# ST_LINK_V2-1.net
KiCad netlist of a schematic drawn in Altium Designer
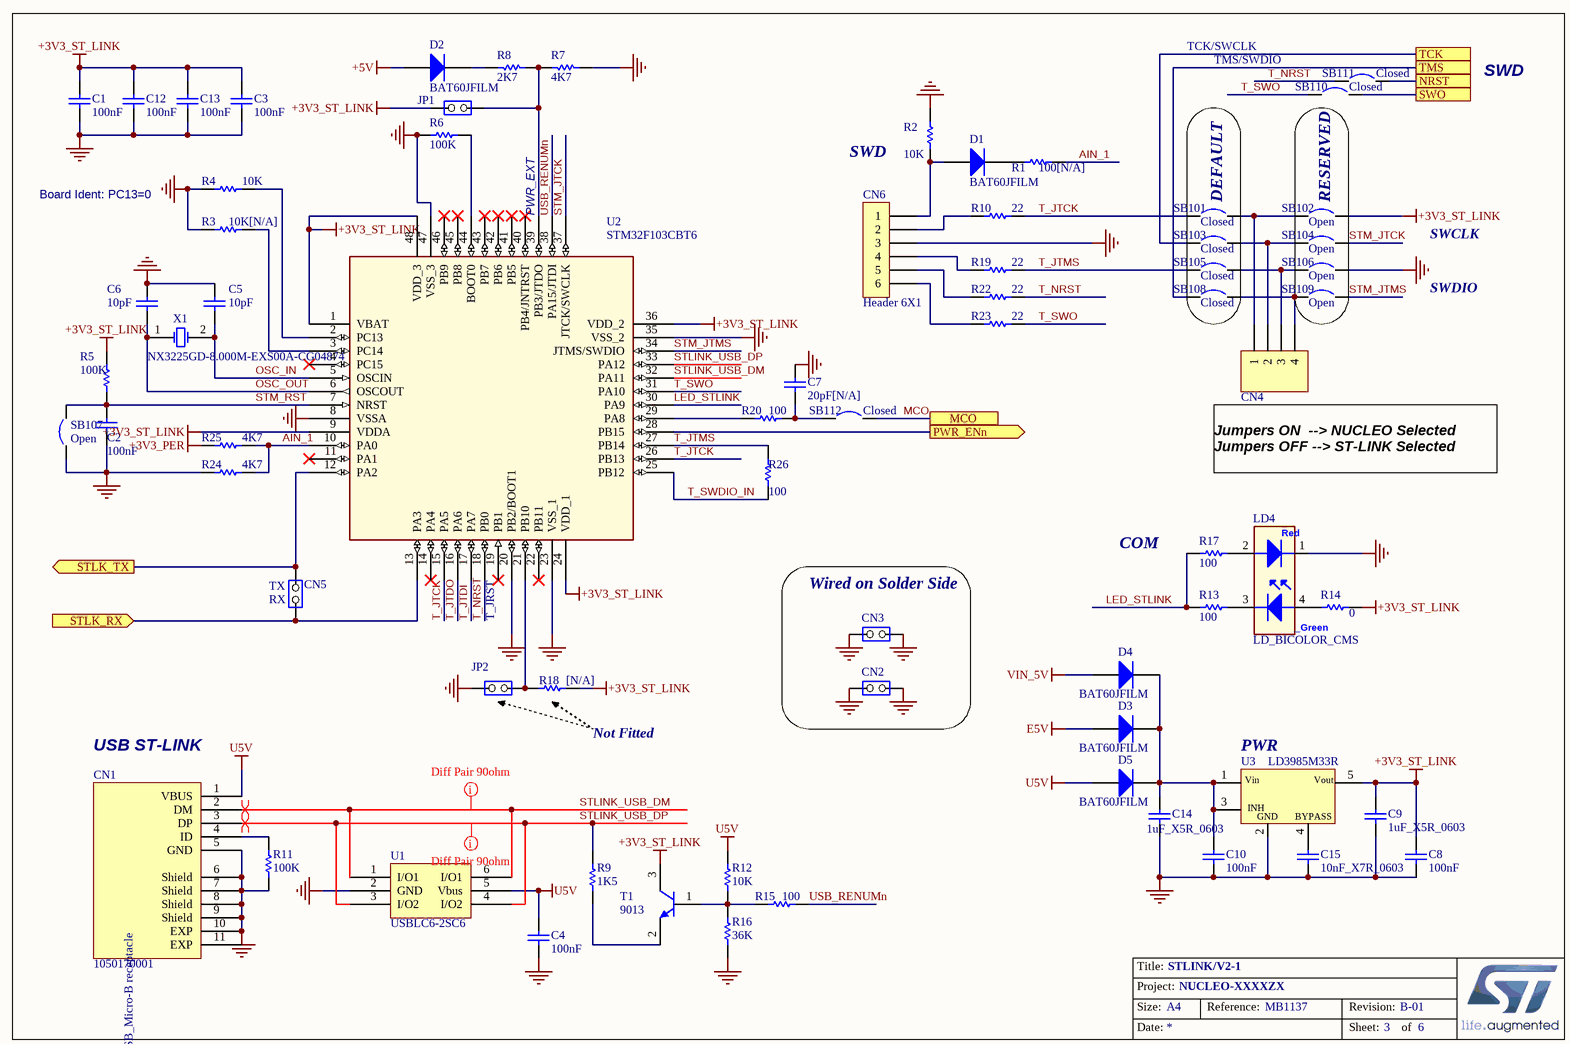
[diagram p0: ST_LINK_V2-1.SCHDOC]

(export (version "E")
  (design (tool "Eeschema 10.0.6"))
  (components
    (comp (ref "C1")
      (value "100nF")
      (footprint "0603C")
      (description "Capacitor 0402 / 0603 / 0805")
      (libsource (lib "MCD_TOOLS") (part "Capacitor_ST"))
    )
    (comp (ref "C2")
      (value "100nF")
      (footprint "0603C")
      (description "Capacitor 0402 / 0603 / 0805")
      (libsource (lib "MCD_TOOLS") (part "Capacitor_ST"))
    )
    (comp (ref "C3")
      (value "100nF")
      (footprint "0603C")
      (description "Capacitor 0402 / 0603 / 0805")
      (libsource (lib "MCD_TOOLS") (part "Capacitor_ST"))
    )
    (comp (ref "C4")
      (value "100nF")
      (footprint "0603C")
      (description "Capacitor 0402 / 0603 / 0805")
      (libsource (lib "MCD_TOOLS") (part "Capacitor_ST"))
    )
    (comp (ref "C5")
      (value "10pF")
      (footprint "0603C")
      (description "Capacitor 0402 / 0603 / 0805")
      (libsource (lib "MCD_TOOLS") (part "Capacitor_ST"))
    )
    (comp (ref "C6")
      (value "10pF")
      (footprint "0603C")
      (description "Capacitor 0402 / 0603 / 0805")
      (libsource (lib "MCD_TOOLS") (part "Capacitor_ST"))
    )
    (comp (ref "C7")
      (value "20pF[N/A]")
      (footprint "0603C")
      (description "Capacitor 0402 / 0603 / 0805")
      (libsource (lib "MCD_TOOLS") (part "Capacitor_ST"))
    )
    (comp (ref "C8")
      (value "100nF")
      (footprint "0603C")
      (description "Capacitor 0402 / 0603 / 0805")
      (libsource (lib "MCD_TOOLS") (part "Capacitor_ST"))
    )
    (comp (ref "C9")
      (value "1uF_X5R_0603")
      (footprint "0603C")
      (description "0603  X5R 1礔")
      (fields (field (name "TOLERANCE") "10%"))
      (libsource (lib "MB963_1") (part "CAP SMD 0603  X5R 1礔 25V 10%"))
    )
    (comp (ref "C10")
      (value "100nF")
      (footprint "0603C")
      (description "Capacitor 0402 / 0603 / 0805")
      (libsource (lib "MCD_TOOLS") (part "Capacitor_ST"))
    )
    (comp (ref "C12")
      (value "100nF")
      (footprint "0603C")
      (description "Capacitor 0402 / 0603 / 0805")
      (libsource (lib "MCD_TOOLS") (part "Capacitor_ST"))
    )
    (comp (ref "C13")
      (value "100nF")
      (footprint "0603C")
      (description "Capacitor 0402 / 0603 / 0805")
      (libsource (lib "MCD_TOOLS") (part "Capacitor_ST"))
    )
    (comp (ref "C14")
      (value "1uF_X5R_0603")
      (footprint "0603C")
      (description "0603  X5R 1礔")
      (fields (field (name "TOLERANCE") "10%"))
      (libsource (lib "MB963_1") (part "CAP SMD 0603  X5R 1礔 25V 10%"))
    )
    (comp (ref "C15")
      (value "10nF_X7R_0603")
      (footprint "0603C")
      (description "0603  X7R 10NF")
      (fields (field (name "TOLERANCE") "10%"))
      (libsource (lib "MB963_1") (part "CAP SMD 0603  X7R 10000PF 50V 10%"))
    )
    (comp (ref "CN1")
      (value "1050170001")
      (footprint "Molex_1050170001")
      (libsource (lib "Smartphone_accessory") (part "1050170001"))
    )
    (comp (ref "CN2") (value "~") (footprint "HDR_1x2_2R54_V_M") (libsource (lib "*") (part "JP2")))
    (comp (ref "CN3") (value "~") (footprint "HDR_1x2_2R54_V_M") (libsource (lib "*") (part "JP2")))
    (comp (ref "CN4")
      (value "Header 4")
      (footprint "HDR_1x4_2R54_V_M")
      (description "Header, 4-Pin, Single row")
      (fields (field (name "PUBLISHER") "Altium Limited"))
      (libsource (lib "Nucleo_64") (part "Header 4"))
    )
    (comp (ref "CN5") (value "~") (footprint "HDR_1x2_2R54_V_M_S") (libsource (lib "MCD_TOOLS") (part "JP2")))
    (comp (ref "CN6")
      (value "Header 6X1")
      (footprint "HDR_1x6_2R54_V_M")
      (description "Header, 6-Pin, Single row")
      (fields (field (name "PUBLISHER") "Altium Limited"))
      (libsource (lib "Nucleo_64") (part "Header 6X1"))
    )
    (comp (ref "D1")
      (value "BAT60JFILM")
      (footprint "SOD-323")
      (libsource (lib "MB1137") (part "BAT60JFILM"))
    )
    (comp (ref "D2")
      (value "BAT60JFILM")
      (footprint "SOD-323")
      (description "Default Diode")
      (fields (field (name "PUBLISHER") "Altium Limited"))
      (libsource (lib "MB1144_1") (part "Diode"))
    )
    (comp (ref "D3")
      (value "BAT60JFILM")
      (footprint "SOD-323")
      (libsource (lib "MB1137") (part "BAT60JFILM"))
    )
    (comp (ref "D4")
      (value "BAT60JFILM")
      (footprint "SOD-323")
      (libsource (lib "MB1137") (part "BAT60JFILM"))
    )
    (comp (ref "D5")
      (value "BAT60JFILM")
      (footprint "SOD-323")
      (libsource (lib "MB1137") (part "BAT60JFILM"))
    )
    (comp (ref "JP1") (value "~") (footprint "HDR_1x2_2R54_V_M_S") (libsource (lib "*") (part "JP2")))
    (comp (ref "JP2") (value "~") (footprint "HDR_1x2_2R54_V_M_S") (libsource (lib "*") (part "JP2")))
    (comp (ref "LD4")
      (value "LD_BICOLOR_CMS")
      (footprint "HSMF-A201")
      (description "Bicolor Led")
      (libsource (lib "MB1137") (part "LD_BICOLOR_CMS"))
    )
    (comp (ref "R1")
      (value "100[N/A]")
      (footprint "0603R")
      (description "Resistor 0402 / 0603 / 0805")
      (libsource (lib "Miscellaneous Devices") (part "Res1"))
    )
    (comp (ref "R2")
      (value "10K")
      (footprint "0603R")
      (description "Resistor 0402 / 0603 / 0805")
      (libsource (lib "Miscellaneous Devices") (part "Res1"))
    )
    (comp (ref "R3")
      (value "10K[N/A]")
      (footprint "0603R")
      (description "Resistor 0402 / 0603 / 0805")
      (libsource (lib "Miscellaneous Devices") (part "Res1"))
    )
    (comp (ref "R4")
      (value "10K")
      (footprint "0603R")
      (description "Resistor 0402 / 0603 / 0805")
      (libsource (lib "Miscellaneous Devices") (part "Res1"))
    )
    (comp (ref "R5")
      (value "100K")
      (footprint "0603R")
      (description "Resistor 0402 / 0603 / 0805")
      (libsource (lib "Miscellaneous Devices") (part "Res1"))
    )
    (comp (ref "R6")
      (value "100K")
      (footprint "0603R")
      (description "Resistor 0402 / 0603 / 0805")
      (libsource (lib "Miscellaneous Devices") (part "Res1"))
    )
    (comp (ref "R7")
      (value "4K7")
      (footprint "0603R")
      (description "Resistor")
      (fields (field (name "PUBLISHER") "Altium Limited"))
      (libsource (lib "") (part "Res1_2"))
    )
    (comp (ref "R8")
      (value "2K7")
      (footprint "0603R")
      (description "Resistor")
      (fields (field (name "PUBLISHER") "Altium Limited"))
      (libsource (lib "") (part "Res1_2"))
    )
    (comp (ref "R9")
      (value "1K5")
      (footprint "0603R")
      (description "Resistor 0402 / 0603 / 0805")
      (libsource (lib "Miscellaneous Devices") (part "Res1"))
    )
    (comp (ref "R10")
      (value "22")
      (footprint "0603R")
      (description "Resistor 0402 / 0603 / 0805")
      (libsource (lib "Miscellaneous Devices") (part "Res1"))
    )
    (comp (ref "R11")
      (value "100K")
      (footprint "0603R")
      (description "Resistor 0402 / 0603 / 0805")
      (libsource (lib "Miscellaneous Devices") (part "Res1"))
    )
    (comp (ref "R12")
      (value "10K")
      (footprint "0603R")
      (description "Resistor")
      (fields (field (name "PUBLISHER") "Altium Limited"))
      (libsource (lib "") (part "Res1_1"))
    )
    (comp (ref "R13")
      (value "100")
      (footprint "0603R")
      (description "Resistor 0402 / 0603 / 0805")
      (libsource (lib "Miscellaneous Devices") (part "Res1"))
    )
    (comp (ref "R14")
      (value "0")
      (footprint "0603R")
      (description "Resistor 0402 / 0603 / 0805")
      (libsource (lib "Miscellaneous Devices") (part "Res1"))
    )
    (comp (ref "R15")
      (value "100")
      (footprint "0603R")
      (description "Resistor 0402 / 0603 / 0805")
      (libsource (lib "Miscellaneous Devices") (part "Res1"))
    )
    (comp (ref "R16")
      (value "36K")
      (footprint "0603R")
      (description "Resistor")
      (fields (field (name "PUBLISHER") "Altium Limited"))
      (libsource (lib "") (part "Res1_1"))
    )
    (comp (ref "R17")
      (value "100")
      (footprint "0603R")
      (description "Resistor 0402 / 0603 / 0805")
      (libsource (lib "Miscellaneous Devices") (part "Res1"))
    )
    (comp (ref "R18")
      (value "[N/A]")
      (footprint "0603R")
      (description "Resistor")
      (fields (field (name "PUBLISHER") "Altium Limited"))
      (libsource (lib "") (part "Res1_1"))
    )
    (comp (ref "R19")
      (value "22")
      (footprint "0603R")
      (description "Resistor 0402 / 0603 / 0805")
      (libsource (lib "Miscellaneous Devices") (part "Res1"))
    )
    (comp (ref "R20")
      (value "100")
      (footprint "0603R")
      (description "Resistor 0402 / 0603 / 0805")
      (libsource (lib "Miscellaneous Devices") (part "Res1"))
    )
    (comp (ref "R22")
      (value "22")
      (footprint "0603R")
      (description "Resistor 0402 / 0603 / 0805")
      (libsource (lib "Miscellaneous Devices") (part "Res1"))
    )
    (comp (ref "R23")
      (value "22")
      (footprint "0603R")
      (description "Resistor 0402 / 0603 / 0805")
      (libsource (lib "Miscellaneous Devices") (part "Res1"))
    )
    (comp (ref "R24")
      (value "4K7")
      (footprint "0603R")
      (description "Resistor 0402 / 0603 / 0805")
      (libsource (lib "Miscellaneous Devices") (part "Res1"))
    )
    (comp (ref "R25")
      (value "4K7")
      (footprint "0603R")
      (description "Resistor 0402 / 0603 / 0805")
      (libsource (lib "Miscellaneous Devices") (part "Res1"))
    )
    (comp (ref "R26")
      (value "100")
      (footprint "0603R")
      (description "Resistor 0402 / 0603 / 0805")
      (libsource (lib "Miscellaneous Devices") (part "Res1"))
    )
    (comp (ref "SB101")
      (value "Closed")
      (footprint "SB_0603")
      (description "Circuit Breaker")
      (fields (field (name "PUBLISHER") "Altium Limited"))
      (libsource (lib "MB1167") (part "Circuit Breaker_close"))
    )
    (comp (ref "SB102")
      (value "Open")
      (footprint "SB_0603")
      (description "Circuit Breaker")
      (fields (field (name "PUBLISHER") "Altium Limited"))
      (libsource (lib "MB1167") (part "Circuit Breaker"))
    )
    (comp (ref "SB103")
      (value "Closed")
      (footprint "SB_0603")
      (description "Circuit Breaker")
      (fields (field (name "PUBLISHER") "Altium Limited"))
      (libsource (lib "MB1167") (part "Circuit Breaker_close"))
    )
    (comp (ref "SB104")
      (value "Open")
      (footprint "SB_0603")
      (description "Circuit Breaker")
      (fields (field (name "PUBLISHER") "Altium Limited"))
      (libsource (lib "MB1167") (part "Circuit Breaker"))
    )
    (comp (ref "SB105")
      (value "Closed")
      (footprint "SB_0603")
      (description "Circuit Breaker")
      (fields (field (name "PUBLISHER") "Altium Limited"))
      (libsource (lib "MB1167") (part "Circuit Breaker_close"))
    )
    (comp (ref "SB106")
      (value "Open")
      (footprint "SB_0603")
      (description "Circuit Breaker")
      (fields (field (name "PUBLISHER") "Altium Limited"))
      (libsource (lib "MB1167") (part "Circuit Breaker"))
    )
    (comp (ref "SB107")
      (value "Open")
      (footprint "SB_0603")
      (description "Circuit Breaker")
      (fields (field (name "PUBLISHER") "Altium Limited"))
      (libsource (lib "MB1167") (part "Circuit Breaker"))
    )
    (comp (ref "SB108")
      (value "Closed")
      (footprint "SB_0603")
      (description "Circuit Breaker")
      (fields (field (name "PUBLISHER") "Altium Limited"))
      (libsource (lib "MB1167") (part "Circuit Breaker_close"))
    )
    (comp (ref "SB109")
      (value "Open")
      (footprint "SB_0603")
      (description "Circuit Breaker")
      (fields (field (name "PUBLISHER") "Altium Limited"))
      (libsource (lib "MB1167") (part "Circuit Breaker"))
    )
    (comp (ref "SB110")
      (value "Closed")
      (footprint "SB_0603")
      (description "Circuit Breaker")
      (fields (field (name "PUBLISHER") "Altium Limited"))
      (libsource (lib "MB1167") (part "Circuit Breaker_close"))
    )
    (comp (ref "SB111")
      (value "Closed")
      (footprint "SB_0603")
      (description "Circuit Breaker")
      (fields (field (name "PUBLISHER") "Altium Limited"))
      (libsource (lib "MB1167") (part "Circuit Breaker_close"))
    )
    (comp (ref "SB112")
      (value "Closed")
      (footprint "SB_0603")
      (description "Circuit Breaker")
      (fields (field (name "PUBLISHER") "Altium Limited"))
      (libsource (lib "MB1167") (part "Circuit Breaker_close"))
    )
    (comp (ref "T1")
      (value "9013")
      (footprint "SOT-23")
      (description "NPN Bipolar Transistor")
      (fields (field (name "PUBLISHER") "Altium Limited"))
      (libsource (lib "MB1167") (part "NPN"))
    )
    (comp (ref "U1")
      (value "USBLC6-2SC6")
      (footprint "SOT23-6L")
      (libsource (lib "MB1137") (part "USBLC6-2SC6"))
    )
    (comp (ref "U2")
      (value "STM32F103CBT6")
      (footprint "LQFP48_0R5_7x7")
      (description "Medium-density performance line ARM-based 32-bit MCU with 64KB Flash")
      (libsource (lib "Nucleo_64") (part "STM32F103CBT6"))
    )
    (comp (ref "U3")
      (value "LD3985M33R")
      (footprint "SOT-23-5L")
      (description "Ultra low drop-low noise BiCMOS voltage, regulators low ESR capacitors compatible")
      (libsource (lib "MCD_TOOLS") (part "LD3985M33R"))
    )
    (comp (ref "X1")
      (value "NX3225GD-8.000M-EXS00A-CG04874")
      (footprint "OSC_2SM_3R2x2R5")
      (description "Crystal Oscillator")
      (fields (field (name "PUBLISHER") "Altium Limited"))
      (libsource (lib "MB963_1") (part "XTAL"))
    )
  )
  (nets
    (net (code "1") (name "+3V3_PER") (class "Default")
      (node (ref "R25") (pin "1") (pinfunction "1_1") (pintype "passive"))
    )
    (net (code "2") (name "+3V3_ST_LINK") (class "Default")
      (node (ref "C1") (pin "2") (pinfunction "2_2") (pintype "passive"))
      (node (ref "C12") (pin "2") (pinfunction "2_2") (pintype "passive"))
      (node (ref "C13") (pin "2") (pinfunction "2_2") (pintype "passive"))
      (node (ref "C3") (pin "2") (pinfunction "2_2") (pintype "passive"))
      (node (ref "C8") (pin "2") (pinfunction "2_2") (pintype "passive"))
      (node (ref "C9") (pin "1") (pinfunction "1_1") (pintype "passive"))
      (node (ref "JP1") (pin "1") (pinfunction "COMMON_1") (pintype "passive"))
      (node (ref "R14") (pin "2") (pinfunction "2_2") (pintype "passive"))
      (node (ref "R18") (pin "1") (pinfunction "1_1") (pintype "passive"))
      (node (ref "R5") (pin "2") (pinfunction "2_2") (pintype "passive"))
      (node (ref "SB102") (pin "2") (pinfunction "2_2") (pintype "passive"))
      (node (ref "T1") (pin "3") (pinfunction "C_3") (pintype "passive"))
      (node (ref "U2") (pin "1") (pinfunction "VBAT_1") (pintype "power_in"))
      (node (ref "U2") (pin "24") (pinfunction "VDD_1_24") (pintype "power_in"))
      (node (ref "U2") (pin "36") (pinfunction "VDD_2_36") (pintype "power_in"))
      (node (ref "U2") (pin "48") (pinfunction "VDD_3_48") (pintype "power_in"))
      (node (ref "U2") (pin "9") (pinfunction "VDDA_9") (pintype "power_in"))
      (node (ref "U3") (pin "5") (pinfunction "Vout_5") (pintype "passive"))
    )
    (net (code "3") (name "+5V") (class "Default")
      (node (ref "D2") (pin "1") (pinfunction "A_1") (pintype "passive"))
    )
    (net (code "4") (name "/AIN_1") (class "Default")
      (node (ref "R1") (pin "2") (pinfunction "2_2") (pintype "passive"))
      (node (ref "R24") (pin "2") (pinfunction "2_2") (pintype "passive"))
      (node (ref "R25") (pin "2") (pinfunction "2_2") (pintype "passive"))
      (node (ref "U2") (pin "10") (pinfunction "PA0_10") (pintype "bidirectional"))
    )
    (net (code "5") (name "/LED_STLINK") (class "Default")
      (node (ref "R13") (pin "1") (pinfunction "1_1") (pintype "passive"))
      (node (ref "R17") (pin "1") (pinfunction "1_1") (pintype "passive"))
      (node (ref "U2") (pin "30") (pinfunction "PA9_30") (pintype "bidirectional"))
    )
    (net (code "6") (name "/MCO") (class "Default")
      (node (ref "SB112") (pin "2") (pinfunction "2_2") (pintype "passive"))
    )
    (net (code "7") (name "/NRST") (class "Default")
      (node (ref "SB111") (pin "2") (pinfunction "2_2") (pintype "passive"))
    )
    (net (code "8") (name "/OSC_IN") (class "Default")
      (node (ref "C5") (pin "1") (pinfunction "1_1") (pintype "passive"))
      (node (ref "U2") (pin "5") (pinfunction "OSCIN_5") (pintype "input"))
      (node (ref "X1") (pin "2") (pinfunction "OSC2_2") (pintype "passive"))
    )
    (net (code "9") (name "/OSC_OUT") (class "Default")
      (node (ref "C6") (pin "1") (pinfunction "1_1") (pintype "passive"))
      (node (ref "U2") (pin "6") (pinfunction "OSCOUT_6") (pintype "output"))
      (node (ref "X1") (pin "1") (pinfunction "OSC1_1") (pintype "passive"))
    )
    (net (code "10") (name "/PWR_ENn") (class "Default")
      (node (ref "U2") (pin "28") (pinfunction "PB15_28") (pintype "bidirectional"))
    )
    (net (code "11") (name "/STLINK_USB_DM") (class "Default")
      (node (ref "CN1") (pin "2") (pinfunction "DM_2") (pintype "passive"))
      (node (ref "U1") (pin "1") (pinfunction "I/O1_1") (pintype "passive"))
      (node (ref "U1") (pin "6") (pinfunction "I/O1_6") (pintype "passive"))
      (node (ref "U2") (pin "32") (pinfunction "PA11_32") (pintype "bidirectional"))
    )
    (net (code "12") (name "/STLINK_USB_DP") (class "Default")
      (node (ref "CN1") (pin "3") (pinfunction "DP_3") (pintype "passive"))
      (node (ref "R9") (pin "1") (pinfunction "1_1") (pintype "passive"))
      (node (ref "U1") (pin "3") (pinfunction "I/O2_3") (pintype "passive"))
      (node (ref "U1") (pin "4") (pinfunction "I/O2_4") (pintype "passive"))
      (node (ref "U2") (pin "33") (pinfunction "PA12_33") (pintype "bidirectional"))
    )
    (net (code "13") (name "/STLK_RX") (class "Default")
      (node (ref "CN5") (pin "1") (pinfunction "COMMON_1") (pintype "passive"))
      (node (ref "U2") (pin "13") (pinfunction "PA3_13") (pintype "bidirectional"))
    )
    (net (code "14") (name "/STLK_TX") (class "Default")
      (node (ref "CN5") (pin "2") (pinfunction "NO_2") (pintype "passive"))
      (node (ref "U2") (pin "12") (pinfunction "PA2_12") (pintype "bidirectional"))
    )
    (net (code "15") (name "/STM_JTCK") (class "Default")
      (node (ref "SB104") (pin "2") (pinfunction "2_2") (pintype "passive"))
      (node (ref "U2") (pin "37") (pinfunction "JTCK/SWCLK_37") (pintype "bidirectional"))
    )
    (net (code "16") (name "/STM_JTMS") (class "Default")
      (node (ref "SB109") (pin "2") (pinfunction "2_2") (pintype "passive"))
      (node (ref "U2") (pin "34") (pinfunction "JTMS/SWDIO_34") (pintype "bidirectional"))
    )
    (net (code "17") (name "/STM_RST") (class "Default")
      (node (ref "C2") (pin "2") (pinfunction "2_2") (pintype "passive"))
      (node (ref "R5") (pin "1") (pinfunction "1_1") (pintype "passive"))
      (node (ref "SB107") (pin "2") (pinfunction "2_2") (pintype "passive"))
      (node (ref "U2") (pin "7") (pinfunction "NRST_7") (pintype "input"))
    )
    (net (code "18") (name "/SWO") (class "Default")
      (node (ref "SB110") (pin "2") (pinfunction "2_2") (pintype "passive"))
    )
    (net (code "19") (name "/TCK") (class "Default")
      (node (ref "SB103") (pin "1") (pinfunction "1_1") (pintype "passive"))
    )
    (net (code "20") (name "/TMS") (class "Default")
      (node (ref "SB108") (pin "1") (pinfunction "1_1") (pintype "passive"))
    )
    (net (code "21") (name "/T_JTCK") (class "Default")
      (node (ref "R10") (pin "2") (pinfunction "2_2") (pintype "passive"))
      (node (ref "SB101") (pin "1") (pinfunction "1_1") (pintype "passive"))
      (node (ref "U2") (pin "15") (pinfunction "PA5_15") (pintype "bidirectional"))
      (node (ref "U2") (pin "26") (pinfunction "PB13_26") (pintype "bidirectional"))
    )
    (net (code "22") (name "/T_JTDI") (class "Default")
      (node (ref "U2") (pin "17") (pinfunction "PA7_17") (pintype "bidirectional"))
    )
    (net (code "23") (name "/T_JTDO") (class "Default")
      (node (ref "U2") (pin "16") (pinfunction "PA6_16") (pintype "bidirectional"))
    )
    (net (code "24") (name "/T_JTMS") (class "Default")
      (node (ref "R19") (pin "2") (pinfunction "2_2") (pintype "passive"))
      (node (ref "R26") (pin "2") (pinfunction "2_2") (pintype "passive"))
      (node (ref "SB105") (pin "1") (pinfunction "1_1") (pintype "passive"))
      (node (ref "U2") (pin "27") (pinfunction "PB14_27") (pintype "bidirectional"))
    )
    (net (code "25") (name "/T_NRST") (class "Default")
      (node (ref "R22") (pin "2") (pinfunction "2_2") (pintype "passive"))
      (node (ref "SB111") (pin "1") (pinfunction "1_1") (pintype "passive"))
      (node (ref "U2") (pin "18") (pinfunction "PB0_18") (pintype "bidirectional"))
    )
    (net (code "26") (name "/T_SWDIO_IN") (class "Default")
      (node (ref "R26") (pin "1") (pinfunction "1_1") (pintype "passive"))
      (node (ref "U2") (pin "25") (pinfunction "PB12_25") (pintype "bidirectional"))
    )
    (net (code "27") (name "/T_SWO") (class "Default")
      (node (ref "R23") (pin "2") (pinfunction "2_2") (pintype "passive"))
      (node (ref "SB110") (pin "1") (pinfunction "1_1") (pintype "passive"))
      (node (ref "U2") (pin "31") (pinfunction "PA10_31") (pintype "bidirectional"))
    )
    (net (code "28") (name "/USB_RENUMn") (class "Default")
      (node (ref "R15") (pin "2") (pinfunction "2_2") (pintype "passive"))
      (node (ref "U2") (pin "38") (pinfunction "PA15/JTDI_38") (pintype "bidirectional"))
    )
    (net (code "29") (name "E5V") (class "Default")
      (node (ref "D3") (pin "1") (pinfunction "A_1") (pintype "passive"))
    )
    (net (code "30") (name "GND") (class "Default")
      (node (ref "C1") (pin "1") (pinfunction "1_1") (pintype "passive"))
      (node (ref "C10") (pin "1") (pinfunction "1_1") (pintype "passive"))
      (node (ref "C12") (pin "1") (pinfunction "1_1") (pintype "passive"))
      (node (ref "C13") (pin "1") (pinfunction "1_1") (pintype "passive"))
      (node (ref "C14") (pin "1") (pinfunction "1_1") (pintype "passive"))
      (node (ref "C15") (pin "1") (pinfunction "1_1") (pintype "passive"))
      (node (ref "C2") (pin "1") (pinfunction "1_1") (pintype "passive"))
      (node (ref "C3") (pin "1") (pinfunction "1_1") (pintype "passive"))
      (node (ref "C4") (pin "1") (pinfunction "1_1") (pintype "passive"))
      (node (ref "C5") (pin "2") (pinfunction "2_2") (pintype "passive"))
      (node (ref "C6") (pin "2") (pinfunction "2_2") (pintype "passive"))
      (node (ref "C7") (pin "2") (pinfunction "2_2") (pintype "passive"))
      (node (ref "C8") (pin "1") (pinfunction "1_1") (pintype "passive"))
      (node (ref "C9") (pin "2") (pinfunction "2_2") (pintype "passive"))
      (node (ref "CN1") (pin "10") (pinfunction "EXP_10") (pintype "passive"))
      (node (ref "CN1") (pin "5") (pinfunction "GND_5") (pintype "passive"))
      (node (ref "CN1") (pin "6") (pinfunction "Shield_6") (pintype "passive"))
      (node (ref "CN1") (pin "7") (pinfunction "Shield_7") (pintype "passive"))
      (node (ref "CN1") (pin "8") (pinfunction "Shield_8") (pintype "passive"))
      (node (ref "CN1") (pin "9") (pinfunction "Shield_9") (pintype "passive"))
      (node (ref "CN2") (pin "1") (pinfunction "COMMON_1") (pintype "passive"))
      (node (ref "CN2") (pin "2") (pinfunction "NO_2") (pintype "passive"))
      (node (ref "CN3") (pin "1") (pinfunction "COMMON_1") (pintype "passive"))
      (node (ref "CN3") (pin "2") (pinfunction "NO_2") (pintype "passive"))
      (node (ref "CN6") (pin "3") (pinfunction "3_3") (pintype "passive"))
      (node (ref "JP2") (pin "1") (pinfunction "COMMON_1") (pintype "passive"))
      (node (ref "LD4") (pin "1") (pinfunction "1_1") (pintype "passive"))
      (node (ref "R11") (pin "2") (pinfunction "2_2") (pintype "passive"))
      (node (ref "R16") (pin "1") (pinfunction "1_1") (pintype "passive"))
      (node (ref "R2") (pin "2") (pinfunction "2_2") (pintype "passive"))
      (node (ref "R24") (pin "1") (pinfunction "1_1") (pintype "passive"))
      (node (ref "R3") (pin "1") (pinfunction "1_1") (pintype "passive"))
      (node (ref "R4") (pin "1") (pinfunction "1_1") (pintype "passive"))
      (node (ref "R6") (pin "1") (pinfunction "1_1") (pintype "passive"))
      (node (ref "R7") (pin "2") (pinfunction "2_2") (pintype "passive"))
      (node (ref "SB106") (pin "2") (pinfunction "2_2") (pintype "passive"))
      (node (ref "SB107") (pin "1") (pinfunction "1_1") (pintype "passive"))
      (node (ref "U1") (pin "2") (pinfunction "GND_2") (pintype "passive"))
      (node (ref "U2") (pin "20") (pinfunction "PB2/BOOT1_20") (pintype "bidirectional"))
      (node (ref "U2") (pin "23") (pinfunction "VSS_1_23") (pintype "power_in"))
      (node (ref "U2") (pin "35") (pinfunction "VSS_2_35") (pintype "power_in"))
      (node (ref "U2") (pin "47") (pinfunction "VSS_3_47") (pintype "power_in"))
      (node (ref "U2") (pin "8") (pinfunction "VSSA_8") (pintype "power_in"))
      (node (ref "U3") (pin "2") (pinfunction "GND_2") (pintype "passive"))
    )
    (net (code "31") (name "Net-(C7-Pad1)") (class "Default")
      (node (ref "C7") (pin "1") (pinfunction "1_1") (pintype "passive"))
      (node (ref "R20") (pin "2") (pinfunction "2_2") (pintype "passive"))
      (node (ref "SB112") (pin "1") (pinfunction "1_1") (pintype "passive"))
    )
    (net (code "32") (name "Net-(CN1-ID)") (class "Default")
      (node (ref "CN1") (pin "4") (pinfunction "ID_4") (pintype "passive"))
      (node (ref "R11") (pin "1") (pinfunction "1_1") (pintype "passive"))
    )
    (net (code "33") (name "Net-(CN4-Pad1)") (class "Default")
      (node (ref "CN4") (pin "1") (pinfunction "1_1") (pintype "passive"))
      (node (ref "SB101") (pin "2") (pinfunction "2_2") (pintype "passive"))
      (node (ref "SB102") (pin "1") (pinfunction "1_1") (pintype "passive"))
    )
    (net (code "34") (name "Net-(CN4-Pad2)") (class "Default")
      (node (ref "CN4") (pin "2") (pinfunction "2_2") (pintype "passive"))
      (node (ref "SB103") (pin "2") (pinfunction "2_2") (pintype "passive"))
      (node (ref "SB104") (pin "1") (pinfunction "1_1") (pintype "passive"))
    )
    (net (code "35") (name "Net-(CN4-Pad3)") (class "Default")
      (node (ref "CN4") (pin "3") (pinfunction "3_3") (pintype "passive"))
      (node (ref "SB105") (pin "2") (pinfunction "2_2") (pintype "passive"))
      (node (ref "SB106") (pin "1") (pinfunction "1_1") (pintype "passive"))
    )
    (net (code "36") (name "Net-(CN4-Pad4)") (class "Default")
      (node (ref "CN4") (pin "4") (pinfunction "4_4") (pintype "passive"))
      (node (ref "SB108") (pin "2") (pinfunction "2_2") (pintype "passive"))
      (node (ref "SB109") (pin "1") (pinfunction "1_1") (pintype "passive"))
    )
    (net (code "37") (name "Net-(CN6-Pad2)") (class "Default")
      (node (ref "CN6") (pin "2") (pinfunction "2_2") (pintype "passive"))
      (node (ref "R10") (pin "1") (pinfunction "1_1") (pintype "passive"))
    )
    (net (code "38") (name "Net-(CN6-Pad4)") (class "Default")
      (node (ref "CN6") (pin "4") (pinfunction "4_4") (pintype "passive"))
      (node (ref "R19") (pin "1") (pinfunction "1_1") (pintype "passive"))
    )
    (net (code "39") (name "Net-(CN6-Pad5)") (class "Default")
      (node (ref "CN6") (pin "5") (pinfunction "5_5") (pintype "passive"))
      (node (ref "R22") (pin "1") (pinfunction "1_1") (pintype "passive"))
    )
    (net (code "40") (name "Net-(CN6-Pad6)") (class "Default")
      (node (ref "CN6") (pin "6") (pinfunction "6_6") (pintype "passive"))
      (node (ref "R23") (pin "1") (pinfunction "1_1") (pintype "passive"))
    )
    (net (code "41") (name "Net-(D1-A)") (class "Default")
      (node (ref "CN6") (pin "1") (pinfunction "1_1") (pintype "passive"))
      (node (ref "D1") (pin "1") (pinfunction "A_1") (pintype "passive"))
      (node (ref "R2") (pin "1") (pinfunction "1_1") (pintype "passive"))
    )
    (net (code "42") (name "Net-(D1-K)") (class "Default")
      (node (ref "D1") (pin "2") (pinfunction "K_2") (pintype "passive"))
      (node (ref "R1") (pin "1") (pinfunction "1_1") (pintype "passive"))
    )
    (net (code "43") (name "Net-(D2-K)") (class "Default")
      (node (ref "D2") (pin "2") (pinfunction "K_2") (pintype "passive"))
      (node (ref "R8") (pin "1") (pinfunction "1_1") (pintype "passive"))
    )
    (net (code "44") (name "Net-(D3-K)") (class "Default")
      (node (ref "C10") (pin "2") (pinfunction "2_2") (pintype "passive"))
      (node (ref "C14") (pin "2") (pinfunction "2_2") (pintype "passive"))
      (node (ref "D3") (pin "2") (pinfunction "K_2") (pintype "passive"))
      (node (ref "D4") (pin "2") (pinfunction "K_2") (pintype "passive"))
      (node (ref "D5") (pin "2") (pinfunction "K_2") (pintype "passive"))
      (node (ref "U3") (pin "1") (pinfunction "Vin_1") (pintype "passive"))
      (node (ref "U3") (pin "3") (pinfunction "CE_3") (pintype "passive"))
    )
    (net (code "45") (name "Net-(JP1-NO)") (class "Default")
      (node (ref "JP1") (pin "2") (pinfunction "NO_2") (pintype "passive"))
      (node (ref "R7") (pin "1") (pinfunction "1_1") (pintype "passive"))
      (node (ref "R8") (pin "2") (pinfunction "2_2") (pintype "passive"))
      (node (ref "U2") (pin "39") (pinfunction "PB3/JTDO_39") (pintype "bidirectional"))
    )
    (net (code "46") (name "Net-(JP2-NO)") (class "Default")
      (node (ref "JP2") (pin "2") (pinfunction "NO_2") (pintype "passive"))
      (node (ref "R18") (pin "2") (pinfunction "2_2") (pintype "passive"))
      (node (ref "U2") (pin "21") (pinfunction "PB10_21") (pintype "bidirectional"))
    )
    (net (code "47") (name "Net-(LD4-Pad2)") (class "Default")
      (node (ref "LD4") (pin "2") (pinfunction "2_2") (pintype "passive"))
      (node (ref "R17") (pin "2") (pinfunction "2_2") (pintype "passive"))
    )
    (net (code "48") (name "Net-(LD4-Pad3)") (class "Default")
      (node (ref "LD4") (pin "3") (pinfunction "3_3") (pintype "passive"))
      (node (ref "R13") (pin "2") (pinfunction "2_2") (pintype "passive"))
    )
    (net (code "49") (name "Net-(LD4-Pad4)") (class "Default")
      (node (ref "LD4") (pin "4") (pinfunction "4_4") (pintype "passive"))
      (node (ref "R14") (pin "1") (pinfunction "1_1") (pintype "passive"))
    )
    (net (code "50") (name "Net-(T1-B)") (class "Default")
      (node (ref "R12") (pin "1") (pinfunction "1_1") (pintype "passive"))
      (node (ref "R15") (pin "1") (pinfunction "1_1") (pintype "passive"))
      (node (ref "R16") (pin "2") (pinfunction "2_2") (pintype "passive"))
      (node (ref "T1") (pin "1") (pinfunction "B_1") (pintype "passive"))
    )
    (net (code "51") (name "Net-(T1-E)") (class "Default")
      (node (ref "R9") (pin "2") (pinfunction "2_2") (pintype "passive"))
      (node (ref "T1") (pin "2") (pinfunction "E_2") (pintype "passive"))
    )
    (net (code "52") (name "Net-(U2-BOOT0)") (class "Default")
      (node (ref "R6") (pin "2") (pinfunction "2_2") (pintype "passive"))
      (node (ref "U2") (pin "44") (pinfunction "BOOT0_44") (pintype "bidirectional"))
    )
    (net (code "53") (name "Net-(U2-PA8)") (class "Default")
      (node (ref "R20") (pin "1") (pinfunction "1_1") (pintype "passive"))
      (node (ref "U2") (pin "29") (pinfunction "PA8_29") (pintype "bidirectional"))
    )
    (net (code "54") (name "Net-(U2-PC13)") (class "Default")
      (node (ref "R4") (pin "2") (pinfunction "2_2") (pintype "passive"))
      (node (ref "U2") (pin "2") (pinfunction "PC13_2") (pintype "bidirectional"))
    )
    (net (code "55") (name "Net-(U2-PC14)") (class "Default")
      (node (ref "R3") (pin "2") (pinfunction "2_2") (pintype "passive"))
      (node (ref "U2") (pin "3") (pinfunction "PC14_3") (pintype "bidirectional"))
    )
    (net (code "56") (name "Net-(U3-BYPASS)") (class "Default")
      (node (ref "C15") (pin "2") (pinfunction "2_2") (pintype "passive"))
      (node (ref "U3") (pin "4") (pinfunction "BYPASS_4") (pintype "passive"))
    )
    (net (code "57") (name "U5V") (class "Default")
      (node (ref "C4") (pin "2") (pinfunction "2_2") (pintype "passive"))
      (node (ref "CN1") (pin "1") (pinfunction "VBUS_1") (pintype "passive"))
      (node (ref "D5") (pin "1") (pinfunction "A_1") (pintype "passive"))
      (node (ref "R12") (pin "2") (pinfunction "2_2") (pintype "passive"))
      (node (ref "U1") (pin "5") (pinfunction "Vbus_5") (pintype "passive"))
    )
    (net (code "58") (name "VIN_5V") (class "Default")
      (node (ref "D4") (pin "1") (pinfunction "A_1") (pintype "passive"))
    )
    (net (code "59") (name "unconnected-(CN1-EXP-Pad11)") (class "Default")
      (node (ref "CN1") (pin "11") (pinfunction "EXP_11") (pintype "passive"))
    )
    (net (code "60") (name "unconnected-(U2-PA1-Pad11)") (class "Default")
      (node (ref "U2") (pin "11") (pinfunction "PA1_11") (pintype "bidirectional+no_connect"))
    )
    (net (code "61") (name "unconnected-(U2-PA4-Pad14)") (class "Default")
      (node (ref "U2") (pin "14") (pinfunction "PA4_14") (pintype "bidirectional+no_connect"))
    )
    (net (code "62") (name "unconnected-(U2-PB1-Pad19)") (class "Default")
      (node (ref "U2") (pin "19") (pinfunction "PB1_19") (pintype "input+no_connect"))
    )
    (net (code "63") (name "unconnected-(U2-PB4{slash}JNTRST-Pad40)") (class "Default")
      (node (ref "U2") (pin "40") (pinfunction "PB4/JNTRST_40") (pintype "bidirectional+no_connect"))
    )
    (net (code "64") (name "unconnected-(U2-PB5-Pad41)") (class "Default")
      (node (ref "U2") (pin "41") (pinfunction "PB5_41") (pintype "bidirectional+no_connect"))
    )
    (net (code "65") (name "unconnected-(U2-PB6-Pad42)") (class "Default")
      (node (ref "U2") (pin "42") (pinfunction "PB6_42") (pintype "bidirectional+no_connect"))
    )
    (net (code "66") (name "unconnected-(U2-PB7-Pad43)") (class "Default")
      (node (ref "U2") (pin "43") (pinfunction "PB7_43") (pintype "bidirectional+no_connect"))
    )
    (net (code "67") (name "unconnected-(U2-PB8-Pad45)") (class "Default")
      (node (ref "U2") (pin "45") (pinfunction "PB8_45") (pintype "bidirectional+no_connect"))
    )
    (net (code "68") (name "unconnected-(U2-PB9-Pad46)") (class "Default")
      (node (ref "U2") (pin "46") (pinfunction "PB9_46") (pintype "bidirectional+no_connect"))
    )
    (net (code "69") (name "unconnected-(U2-PB11-Pad22)") (class "Default")
      (node (ref "U2") (pin "22") (pinfunction "PB11_22") (pintype "bidirectional+no_connect"))
    )
    (net (code "70") (name "unconnected-(U2-PC15-Pad4)") (class "Default")
      (node (ref "U2") (pin "4") (pinfunction "PC15_4") (pintype "bidirectional+no_connect"))
    )
  )
)
